# CHAIRI2C.net
KiCad netlist of a schematic drawn in EAGLE
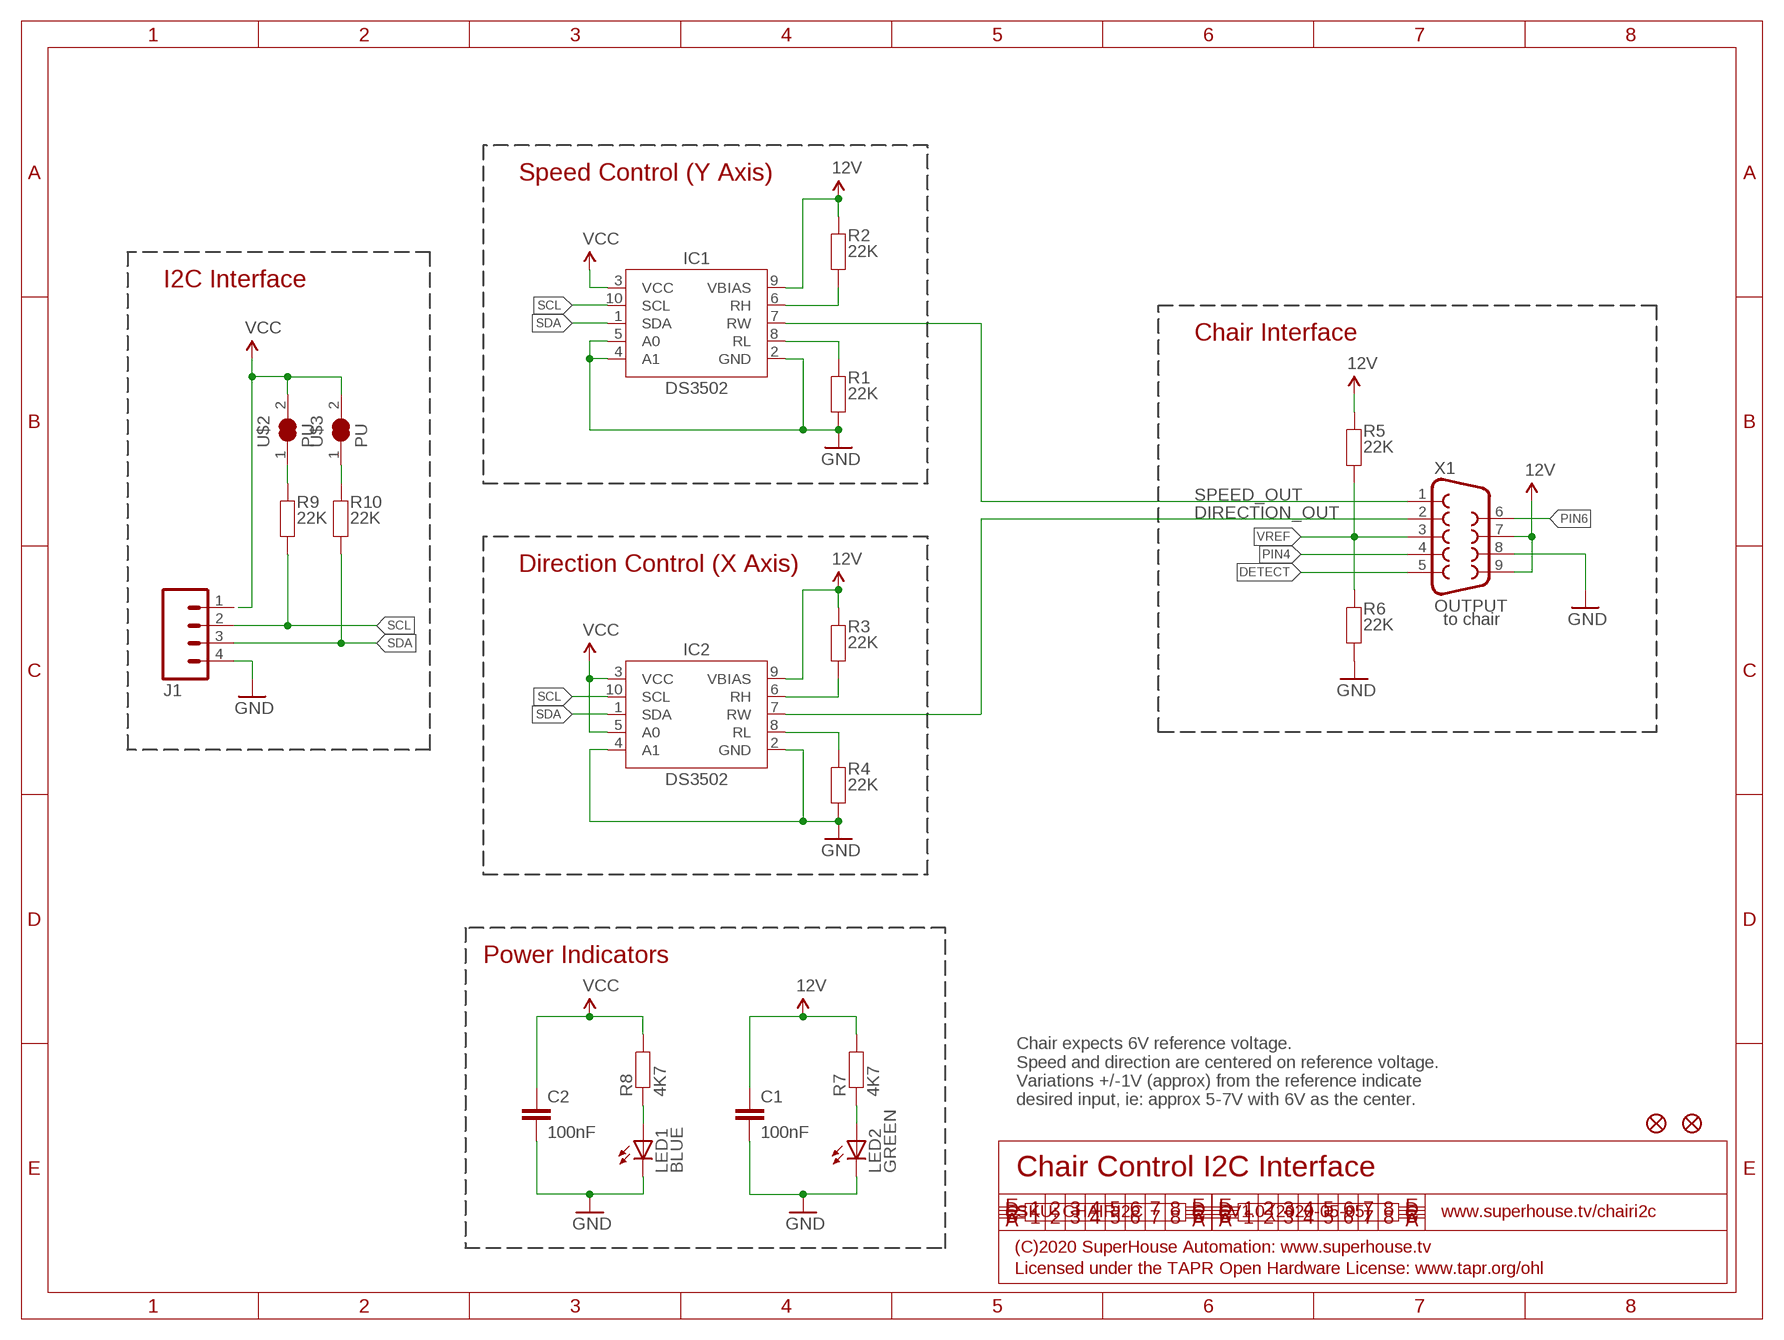
[diagram p0: schematic, sheet 1]

(export (version "E")
  (design (tool "Eeschema 10.0.6"))
  (components
    (comp (ref "C1")
      (value "100nF")
      (footprint "eagle-import:C0603")
      (libsource (lib "eagle-import") (part "CAP0603"))
    )
    (comp (ref "C2")
      (value "100nF")
      (footprint "eagle-import:C0603")
      (libsource (lib "eagle-import") (part "CAP0603"))
    )
    (comp (ref "IC1")
      (value "DS3502")
      (footprint "eagle-import:MSOP10")
      (libsource (lib "eagle-import") (part "DS3502"))
    )
    (comp (ref "IC2")
      (value "DS3502")
      (footprint "eagle-import:MSOP10")
      (libsource (lib "eagle-import") (part "DS3502"))
    )
    (comp (ref "J1")
      (value "M04-PLAIN")
      (footprint "eagle-import:1X04")
      (libsource (lib "eagle-import") (part "M04-PLAIN"))
    )
    (comp (ref "LED1")
      (value "BLUE")
      (footprint "eagle-import:LED-0603")
      (libsource (lib "eagle-import") (part "LED0603"))
    )
    (comp (ref "LED2")
      (value "GREEN")
      (footprint "eagle-import:LED-0603")
      (libsource (lib "eagle-import") (part "LED0603"))
    )
    (comp (ref "R1")
      (value "22K")
      (footprint "eagle-import:R0603")
      (libsource (lib "eagle-import") (part "RESISTOR0603"))
    )
    (comp (ref "R2")
      (value "22K")
      (footprint "eagle-import:R0603")
      (libsource (lib "eagle-import") (part "RESISTOR0603"))
    )
    (comp (ref "R3")
      (value "22K")
      (footprint "eagle-import:R0603")
      (libsource (lib "eagle-import") (part "RESISTOR0603"))
    )
    (comp (ref "R4")
      (value "22K")
      (footprint "eagle-import:R0603")
      (libsource (lib "eagle-import") (part "RESISTOR0603"))
    )
    (comp (ref "R5")
      (value "22K")
      (footprint "eagle-import:R0603")
      (libsource (lib "eagle-import") (part "RESISTOR0603"))
    )
    (comp (ref "R6")
      (value "22K")
      (footprint "eagle-import:R0603")
      (libsource (lib "eagle-import") (part "RESISTOR0603"))
    )
    (comp (ref "R7")
      (value "4K7")
      (footprint "eagle-import:R0603")
      (libsource (lib "eagle-import") (part "RESISTOR0603"))
    )
    (comp (ref "R8")
      (value "4K7")
      (footprint "eagle-import:R0603")
      (libsource (lib "eagle-import") (part "RESISTOR0603"))
    )
    (comp (ref "R9")
      (value "22K")
      (footprint "eagle-import:R0603")
      (libsource (lib "eagle-import") (part "RESISTOR0603"))
    )
    (comp (ref "R10")
      (value "22K")
      (footprint "eagle-import:R0603")
      (libsource (lib "eagle-import") (part "RESISTOR0603"))
    )
    (comp (ref "U$2")
      (value "PU")
      (footprint "eagle-import:SJC")
      (libsource (lib "eagle-import") (part "SJC-NORMAL"))
    )
    (comp (ref "U$3")
      (value "PU")
      (footprint "eagle-import:SJC")
      (libsource (lib "eagle-import") (part "SJC-NORMAL"))
    )
    (comp (ref "U$8")
      (value "FIDUCIAL1X2.5")
      (footprint "eagle-import:FIDUCIAL-1X2.5")
      (libsource (lib "eagle-import") (part "FIDUCIAL1X2.5"))
    )
    (comp (ref "U$9")
      (value "FIDUCIAL1X2.5")
      (footprint "eagle-import:FIDUCIAL-1X2.5")
      (libsource (lib "eagle-import") (part "FIDUCIAL1X2.5"))
    )
    (comp (ref "X1")
      (value "OUTPUT")
      (footprint "eagle-import:DB9-PCB-SOCKET")
      (libsource (lib "eagle-import") (part "DB9-PCB-SOCKET"))
    )
  )
  (nets
    (net (code "1") (name "/DIRECTION_OUT") (class "Default")
      (node (ref "IC2") (pin "7") (pinfunction "RW_7") (pintype "passive"))
      (node (ref "X1") (pin "2") (pinfunction "2_2") (pintype "passive"))
    )
    (net (code "2") (name "/SPEED_OUT") (class "Default")
      (node (ref "IC1") (pin "7") (pinfunction "RW_7") (pintype "passive"))
      (node (ref "X1") (pin "1") (pinfunction "1_1") (pintype "passive"))
    )
    (net (code "3") (name "12V") (class "Default")
      (node (ref "C1") (pin "1") (pinfunction "1_1") (pintype "passive"))
      (node (ref "IC1") (pin "9") (pinfunction "VBIAS_9") (pintype "power_in"))
      (node (ref "IC2") (pin "9") (pinfunction "VBIAS_9") (pintype "power_in"))
      (node (ref "R2") (pin "2") (pinfunction "2_2") (pintype "passive"))
      (node (ref "R3") (pin "2") (pinfunction "2_2") (pintype "passive"))
      (node (ref "R5") (pin "2") (pinfunction "2_2") (pintype "passive"))
      (node (ref "R7") (pin "2") (pinfunction "2_2") (pintype "passive"))
      (node (ref "X1") (pin "7") (pinfunction "7_7") (pintype "passive"))
      (node (ref "X1") (pin "9") (pinfunction "9_9") (pintype "passive"))
    )
    (net (code "4") (name "DETECT") (class "Default")
      (node (ref "X1") (pin "5") (pinfunction "5_5") (pintype "passive"))
    )
    (net (code "5") (name "GND") (class "Default")
      (node (ref "C1") (pin "2") (pinfunction "2_2") (pintype "passive"))
      (node (ref "C2") (pin "2") (pinfunction "2_2") (pintype "passive"))
      (node (ref "IC1") (pin "2") (pinfunction "GND_2") (pintype "power_in"))
      (node (ref "IC1") (pin "4") (pinfunction "A1_4") (pintype "input"))
      (node (ref "IC1") (pin "5") (pinfunction "A0_5") (pintype "input"))
      (node (ref "IC2") (pin "2") (pinfunction "GND_2") (pintype "power_in"))
      (node (ref "IC2") (pin "4") (pinfunction "A1_4") (pintype "input"))
      (node (ref "J1") (pin "4") (pinfunction "4_4") (pintype "passive"))
      (node (ref "LED1") (pin "C") (pinfunction "C_C") (pintype "passive"))
      (node (ref "LED2") (pin "C") (pinfunction "C_C") (pintype "passive"))
      (node (ref "R1") (pin "1") (pinfunction "1_1") (pintype "passive"))
      (node (ref "R4") (pin "1") (pinfunction "1_1") (pintype "passive"))
      (node (ref "R6") (pin "1") (pinfunction "1_1") (pintype "passive"))
      (node (ref "X1") (pin "8") (pinfunction "8_8") (pintype "passive"))
    )
    (net (code "6") (name "Net-(IC1-RH)") (class "Default")
      (node (ref "IC1") (pin "6") (pinfunction "RH_6") (pintype "passive"))
      (node (ref "R2") (pin "1") (pinfunction "1_1") (pintype "passive"))
    )
    (net (code "7") (name "Net-(IC1-RL)") (class "Default")
      (node (ref "IC1") (pin "8") (pinfunction "RL_8") (pintype "passive"))
      (node (ref "R1") (pin "2") (pinfunction "2_2") (pintype "passive"))
    )
    (net (code "8") (name "Net-(IC2-RH)") (class "Default")
      (node (ref "IC2") (pin "6") (pinfunction "RH_6") (pintype "passive"))
      (node (ref "R3") (pin "1") (pinfunction "1_1") (pintype "passive"))
    )
    (net (code "9") (name "Net-(IC2-RL)") (class "Default")
      (node (ref "IC2") (pin "8") (pinfunction "RL_8") (pintype "passive"))
      (node (ref "R4") (pin "2") (pinfunction "2_2") (pintype "passive"))
    )
    (net (code "10") (name "Net-(LED1-PadA)") (class "Default")
      (node (ref "LED1") (pin "A") (pinfunction "A_A") (pintype "passive"))
      (node (ref "R8") (pin "1") (pinfunction "1_1") (pintype "passive"))
    )
    (net (code "11") (name "Net-(LED2-PadA)") (class "Default")
      (node (ref "LED2") (pin "A") (pinfunction "A_A") (pintype "passive"))
      (node (ref "R7") (pin "1") (pinfunction "1_1") (pintype "passive"))
    )
    (net (code "12") (name "Net-(R9-Pad2)") (class "Default")
      (node (ref "R9") (pin "2") (pinfunction "2_2") (pintype "passive"))
      (node (ref "U$2") (pin "1") (pinfunction "1_1") (pintype "passive"))
    )
    (net (code "13") (name "Net-(R10-Pad2)") (class "Default")
      (node (ref "R10") (pin "2") (pinfunction "2_2") (pintype "passive"))
      (node (ref "U$3") (pin "1") (pinfunction "1_1") (pintype "passive"))
    )
    (net (code "14") (name "PIN4") (class "Default")
      (node (ref "X1") (pin "4") (pinfunction "4_4") (pintype "passive"))
    )
    (net (code "15") (name "PIN6") (class "Default")
      (node (ref "X1") (pin "6") (pinfunction "6_6") (pintype "passive"))
    )
    (net (code "16") (name "SCL") (class "Default")
      (node (ref "IC1") (pin "10") (pinfunction "SCL_10") (pintype "input"))
      (node (ref "IC2") (pin "10") (pinfunction "SCL_10") (pintype "input"))
      (node (ref "J1") (pin "2") (pinfunction "2_2") (pintype "passive"))
      (node (ref "R9") (pin "1") (pinfunction "1_1") (pintype "passive"))
    )
    (net (code "17") (name "SDA") (class "Default")
      (node (ref "IC1") (pin "1") (pinfunction "SDA_1") (pintype "bidirectional"))
      (node (ref "IC2") (pin "1") (pinfunction "SDA_1") (pintype "bidirectional"))
      (node (ref "J1") (pin "3") (pinfunction "3_3") (pintype "passive"))
      (node (ref "R10") (pin "1") (pinfunction "1_1") (pintype "passive"))
    )
    (net (code "18") (name "VCC") (class "Default")
      (node (ref "C2") (pin "1") (pinfunction "1_1") (pintype "passive"))
      (node (ref "IC1") (pin "3") (pinfunction "VCC_3") (pintype "power_in"))
      (node (ref "IC2") (pin "3") (pinfunction "VCC_3") (pintype "power_in"))
      (node (ref "IC2") (pin "5") (pinfunction "A0_5") (pintype "input"))
      (node (ref "J1") (pin "1") (pinfunction "1_1") (pintype "passive"))
      (node (ref "R8") (pin "2") (pinfunction "2_2") (pintype "passive"))
      (node (ref "U$2") (pin "2") (pinfunction "2_2") (pintype "passive"))
      (node (ref "U$3") (pin "2") (pinfunction "2_2") (pintype "passive"))
    )
    (net (code "19") (name "VREF") (class "Default")
      (node (ref "R5") (pin "1") (pinfunction "1_1") (pintype "passive"))
      (node (ref "R6") (pin "2") (pinfunction "2_2") (pintype "passive"))
      (node (ref "X1") (pin "3") (pinfunction "3_3") (pintype "passive"))
    )
  )
)
